# AFPGA_power.net
KiCad netlist of a schematic drawn in Altium Designer
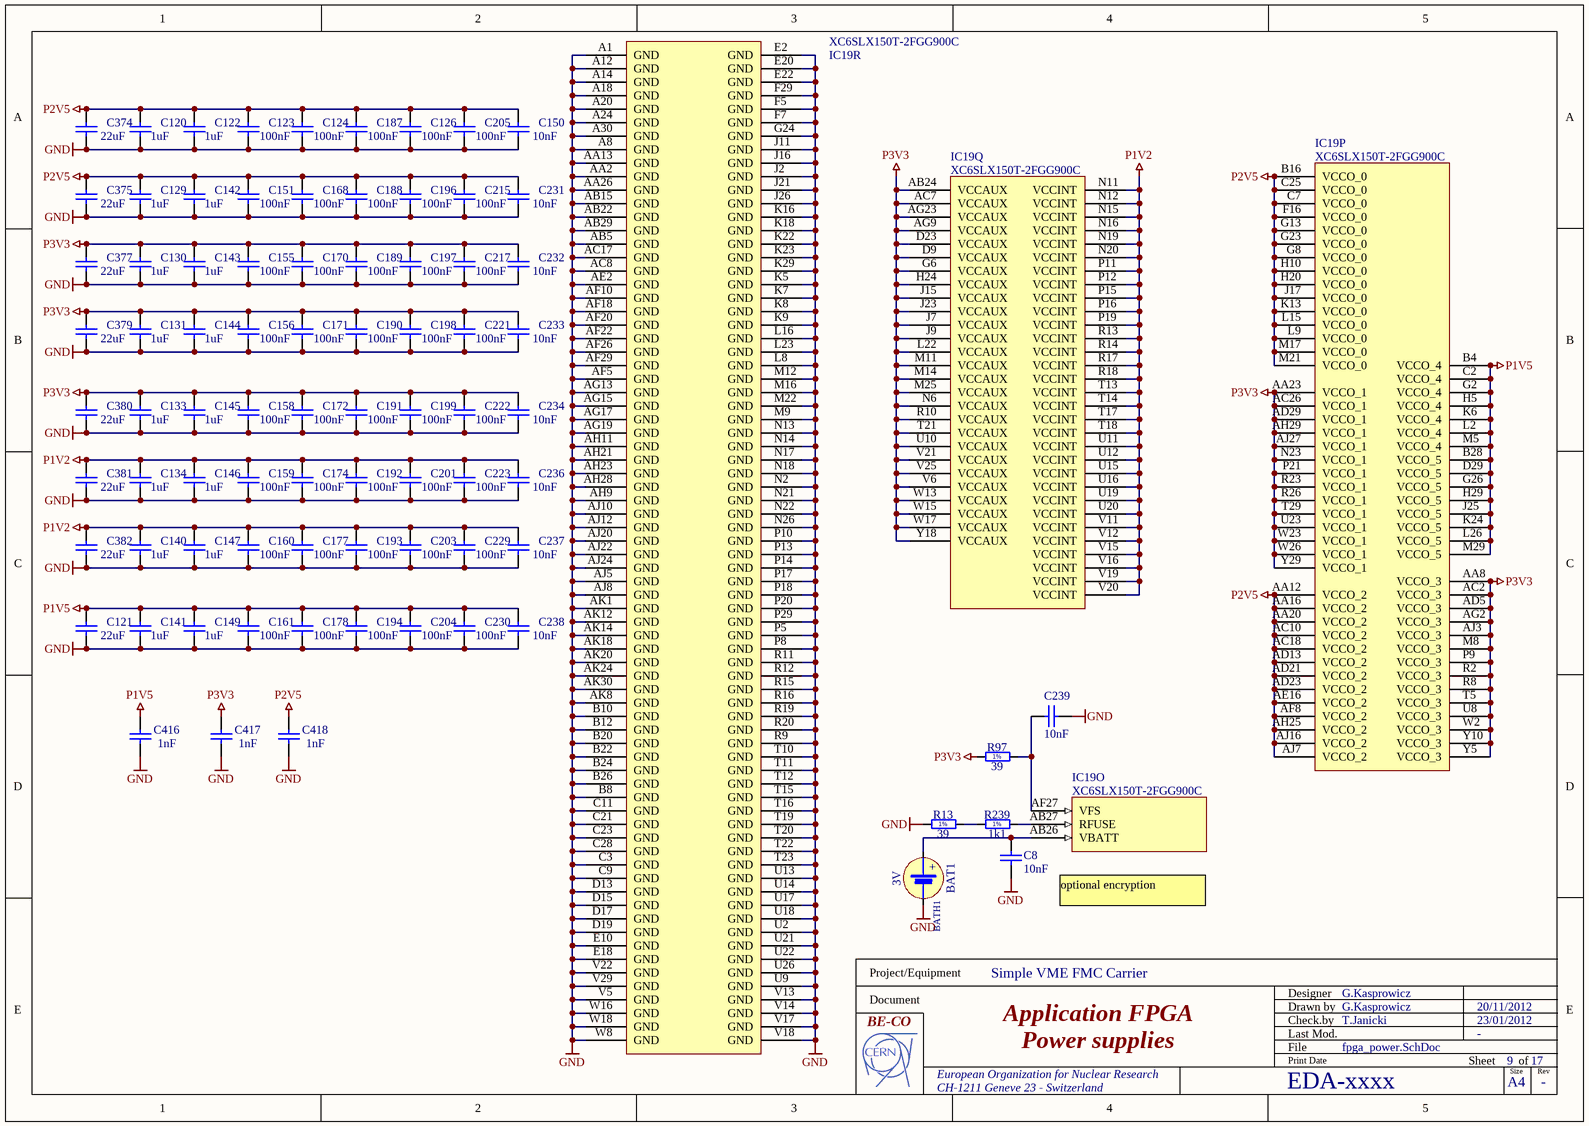
[diagram p0: AFPGA_power.SchDoc]

(export (version "E")
  (design (tool "Eeschema 10.0.6"))
  (components
    (comp (ref "BAT1")
      (value "3V")
      (footprint "BAT_VARTA_CR2025")
      (description "Battery for use only with Socket Holder")
      (fields
        (field (name "PART NUMBER") "BAT_VARTA_CR2025")
        (field (name "POWER") "165mAh")
        (field (name "AUTHOR") "CERN DEM JLC")
      )
      (libsource (lib "Eletro-mechanical") (part "Battery No Pin"))
    )
    (comp (ref "BATH1")
      (value "~")
      (footprint "BATH_KEYSTONE_103")
      (description "Battery Holder whit 2 Pin")
      (fields
        (field (name "PART NUMBER") "BATH_KEYSTONE_103")
        (field (name "MANUFACTURER") "KEYSTONE")
        (field (name "AUTHOR") "CERN DEM JLC")
      )
      (libsource (lib "Eletro-mechanical") (part "Battery Holder 2 Pin"))
    )
    (comp (ref "C8")
      (value "10nF")
      (footprint "CAPC1608X87N")
      (description "Non-polarised capacitor")
      (fields
        (field (name "PART NUMBER") "CC0603_10NF_50V_10%_X7R")
        (field (name "VOLTAGE") "50V")
        (field (name "AUTHOR") "CERN DEM JLC")
      )
      (libsource (lib "Capacitors") (part "Capacitor - non polarized"))
    )
    (comp (ref "C120")
      (value "1uF")
      (footprint "CAPC1608X87N")
      (description "Non-polarised capacitor")
      (fields
        (field (name "PART NUMBER") "CC0603_1UF_16V_10%_X7R")
        (field (name "VOLTAGE") "16V")
        (field (name "AUTHOR") "CERN DEM JLC")
      )
      (libsource (lib "Capacitors") (part "Capacitor - non polarized"))
    )
    (comp (ref "C121")
      (value "22uF")
      (footprint "CAPC3216X180N")
      (description "Non-polarised capacitor")
      (fields
        (field (name "PART NUMBER") "CC1206_22UF_10V_10%_X7R")
        (field (name "VOLTAGE") "10V")
        (field (name "AUTHOR") "CERN DEM JLC")
      )
      (libsource (lib "Capacitors") (part "Capacitor - non polarized"))
    )
    (comp (ref "C122")
      (value "1uF")
      (footprint "CAPC1608X87N")
      (description "Non-polarised capacitor")
      (fields
        (field (name "PART NUMBER") "CC0603_1UF_16V_10%_X7R")
        (field (name "VOLTAGE") "16V")
        (field (name "AUTHOR") "CERN DEM JLC")
      )
      (libsource (lib "Capacitors") (part "Capacitor - non polarized"))
    )
    (comp (ref "C123")
      (value "100nF")
      (footprint "CAPC1005X55N")
      (description "Non-polarised capacitor")
      (fields
        (field (name "PART NUMBER") "CC0402_100NF_16V_10%_X7R")
        (field (name "VOLTAGE") "16V")
        (field (name "AUTHOR") "CERN DEM JLC")
      )
      (libsource (lib "Capacitors") (part "Capacitor - non polarized"))
    )
    (comp (ref "C124")
      (value "100nF")
      (footprint "CAPC1005X55N")
      (description "Non-polarised capacitor")
      (fields
        (field (name "PART NUMBER") "CC0402_100NF_16V_10%_X7R")
        (field (name "VOLTAGE") "16V")
        (field (name "AUTHOR") "CERN DEM JLC")
      )
      (libsource (lib "Capacitors") (part "Capacitor - non polarized"))
    )
    (comp (ref "C126")
      (value "100nF")
      (footprint "CAPC1005X55N")
      (description "Non-polarised capacitor")
      (fields
        (field (name "PART NUMBER") "CC0402_100NF_16V_10%_X7R")
        (field (name "VOLTAGE") "16V")
        (field (name "AUTHOR") "CERN DEM JLC")
      )
      (libsource (lib "Capacitors") (part "Capacitor - non polarized"))
    )
    (comp (ref "C129")
      (value "1uF")
      (footprint "CAPC1608X87N")
      (description "Non-polarised capacitor")
      (fields
        (field (name "PART NUMBER") "CC0603_1UF_16V_10%_X7R")
        (field (name "VOLTAGE") "16V")
        (field (name "AUTHOR") "CERN DEM JLC")
      )
      (libsource (lib "Capacitors") (part "Capacitor - non polarized"))
    )
    (comp (ref "C130")
      (value "1uF")
      (footprint "CAPC1608X87N")
      (description "Non-polarised capacitor")
      (fields
        (field (name "PART NUMBER") "CC0603_1UF_16V_10%_X7R")
        (field (name "VOLTAGE") "16V")
        (field (name "AUTHOR") "CERN DEM JLC")
      )
      (libsource (lib "Capacitors") (part "Capacitor - non polarized"))
    )
    (comp (ref "C131")
      (value "1uF")
      (footprint "CAPC1608X87N")
      (description "Non-polarised capacitor")
      (fields
        (field (name "PART NUMBER") "CC0603_1UF_16V_10%_X7R")
        (field (name "VOLTAGE") "16V")
        (field (name "AUTHOR") "CERN DEM JLC")
      )
      (libsource (lib "Capacitors") (part "Capacitor - non polarized"))
    )
    (comp (ref "C133")
      (value "1uF")
      (footprint "CAPC1608X87N")
      (description "Non-polarised capacitor")
      (fields
        (field (name "PART NUMBER") "CC0603_1UF_16V_10%_X7R")
        (field (name "VOLTAGE") "16V")
        (field (name "AUTHOR") "CERN DEM JLC")
      )
      (libsource (lib "Capacitors") (part "Capacitor - non polarized"))
    )
    (comp (ref "C134")
      (value "1uF")
      (footprint "CAPC1608X87N")
      (description "Non-polarised capacitor")
      (fields
        (field (name "PART NUMBER") "CC0603_1UF_16V_10%_X7R")
        (field (name "VOLTAGE") "16V")
        (field (name "AUTHOR") "CERN DEM JLC")
      )
      (libsource (lib "Capacitors") (part "Capacitor - non polarized"))
    )
    (comp (ref "C140")
      (value "1uF")
      (footprint "CAPC1608X87N")
      (description "Non-polarised capacitor")
      (fields
        (field (name "PART NUMBER") "CC0603_1UF_16V_10%_X7R")
        (field (name "VOLTAGE") "16V")
        (field (name "AUTHOR") "CERN DEM JLC")
      )
      (libsource (lib "Capacitors") (part "Capacitor - non polarized"))
    )
    (comp (ref "C141")
      (value "1uF")
      (footprint "CAPC1608X87N")
      (description "Non-polarised capacitor")
      (fields
        (field (name "PART NUMBER") "CC0603_1UF_16V_10%_X7R")
        (field (name "VOLTAGE") "16V")
        (field (name "AUTHOR") "CERN DEM JLC")
      )
      (libsource (lib "Capacitors") (part "Capacitor - non polarized"))
    )
    (comp (ref "C142")
      (value "1uF")
      (footprint "CAPC1608X87N")
      (description "Non-polarised capacitor")
      (fields
        (field (name "PART NUMBER") "CC0603_1UF_16V_10%_X7R")
        (field (name "VOLTAGE") "16V")
        (field (name "AUTHOR") "CERN DEM JLC")
      )
      (libsource (lib "Capacitors") (part "Capacitor - non polarized"))
    )
    (comp (ref "C143")
      (value "1uF")
      (footprint "CAPC1608X87N")
      (description "Non-polarised capacitor")
      (fields
        (field (name "PART NUMBER") "CC0603_1UF_16V_10%_X7R")
        (field (name "VOLTAGE") "16V")
        (field (name "AUTHOR") "CERN DEM JLC")
      )
      (libsource (lib "Capacitors") (part "Capacitor - non polarized"))
    )
    (comp (ref "C144")
      (value "1uF")
      (footprint "CAPC1608X87N")
      (description "Non-polarised capacitor")
      (fields
        (field (name "PART NUMBER") "CC0603_1UF_16V_10%_X7R")
        (field (name "VOLTAGE") "16V")
        (field (name "AUTHOR") "CERN DEM JLC")
      )
      (libsource (lib "Capacitors") (part "Capacitor - non polarized"))
    )
    (comp (ref "C145")
      (value "1uF")
      (footprint "CAPC1608X87N")
      (description "Non-polarised capacitor")
      (fields
        (field (name "PART NUMBER") "CC0603_1UF_16V_10%_X7R")
        (field (name "VOLTAGE") "16V")
        (field (name "AUTHOR") "CERN DEM JLC")
      )
      (libsource (lib "Capacitors") (part "Capacitor - non polarized"))
    )
    (comp (ref "C146")
      (value "1uF")
      (footprint "CAPC1608X87N")
      (description "Non-polarised capacitor")
      (fields
        (field (name "PART NUMBER") "CC0603_1UF_16V_10%_X7R")
        (field (name "VOLTAGE") "16V")
        (field (name "AUTHOR") "CERN DEM JLC")
      )
      (libsource (lib "Capacitors") (part "Capacitor - non polarized"))
    )
    (comp (ref "C147")
      (value "1uF")
      (footprint "CAPC1608X87N")
      (description "Non-polarised capacitor")
      (fields
        (field (name "PART NUMBER") "CC0603_1UF_16V_10%_X7R")
        (field (name "VOLTAGE") "16V")
        (field (name "AUTHOR") "CERN DEM JLC")
      )
      (libsource (lib "Capacitors") (part "Capacitor - non polarized"))
    )
    (comp (ref "C149")
      (value "1uF")
      (footprint "CAPC1608X87N")
      (description "Non-polarised capacitor")
      (fields
        (field (name "PART NUMBER") "CC0603_1UF_16V_10%_X7R")
        (field (name "VOLTAGE") "16V")
        (field (name "AUTHOR") "CERN DEM JLC")
      )
      (libsource (lib "Capacitors") (part "Capacitor - non polarized"))
    )
    (comp (ref "C150")
      (value "10nF")
      (footprint "CAPC1608X87N")
      (description "Non-polarised capacitor")
      (fields
        (field (name "PART NUMBER") "CC0603_10NF_50V_10%_X7R")
        (field (name "VOLTAGE") "50V")
        (field (name "AUTHOR") "CERN DEM JLC")
      )
      (libsource (lib "Capacitors") (part "Capacitor - non polarized"))
    )
    (comp (ref "C151")
      (value "100nF")
      (footprint "CAPC1005X55N")
      (description "Non-polarised capacitor")
      (fields
        (field (name "PART NUMBER") "CC0402_100NF_16V_10%_X7R")
        (field (name "VOLTAGE") "16V")
        (field (name "AUTHOR") "CERN DEM JLC")
      )
      (libsource (lib "Capacitors") (part "Capacitor - non polarized"))
    )
    (comp (ref "C155")
      (value "100nF")
      (footprint "CAPC1005X55N")
      (description "Non-polarised capacitor")
      (fields
        (field (name "PART NUMBER") "CC0402_100NF_16V_10%_X7R")
        (field (name "VOLTAGE") "16V")
        (field (name "AUTHOR") "CERN DEM JLC")
      )
      (libsource (lib "Capacitors") (part "Capacitor - non polarized"))
    )
    (comp (ref "C156")
      (value "100nF")
      (footprint "CAPC1005X55N")
      (description "Non-polarised capacitor")
      (fields
        (field (name "PART NUMBER") "CC0402_100NF_16V_10%_X7R")
        (field (name "VOLTAGE") "16V")
        (field (name "AUTHOR") "CERN DEM JLC")
      )
      (libsource (lib "Capacitors") (part "Capacitor - non polarized"))
    )
    (comp (ref "C158")
      (value "100nF")
      (footprint "CAPC1005X55N")
      (description "Non-polarised capacitor")
      (fields
        (field (name "PART NUMBER") "CC0402_100NF_16V_10%_X7R")
        (field (name "VOLTAGE") "16V")
        (field (name "AUTHOR") "CERN DEM JLC")
      )
      (libsource (lib "Capacitors") (part "Capacitor - non polarized"))
    )
    (comp (ref "C159")
      (value "100nF")
      (footprint "CAPC1005X55N")
      (description "Non-polarised capacitor")
      (fields
        (field (name "PART NUMBER") "CC0402_100NF_16V_10%_X7R")
        (field (name "VOLTAGE") "16V")
        (field (name "AUTHOR") "CERN DEM JLC")
      )
      (libsource (lib "Capacitors") (part "Capacitor - non polarized"))
    )
    (comp (ref "C160")
      (value "100nF")
      (footprint "CAPC1005X55N")
      (description "Non-polarised capacitor")
      (fields
        (field (name "PART NUMBER") "CC0402_100NF_16V_10%_X7R")
        (field (name "VOLTAGE") "16V")
        (field (name "AUTHOR") "CERN DEM JLC")
      )
      (libsource (lib "Capacitors") (part "Capacitor - non polarized"))
    )
    (comp (ref "C161")
      (value "100nF")
      (footprint "CAPC1005X55N")
      (description "Non-polarised capacitor")
      (fields
        (field (name "PART NUMBER") "CC0402_100NF_16V_10%_X7R")
        (field (name "VOLTAGE") "16V")
        (field (name "AUTHOR") "CERN DEM JLC")
      )
      (libsource (lib "Capacitors") (part "Capacitor - non polarized"))
    )
    (comp (ref "C168")
      (value "100nF")
      (footprint "CAPC1005X55N")
      (description "Non-polarised capacitor")
      (fields
        (field (name "PART NUMBER") "CC0402_100NF_16V_10%_X7R")
        (field (name "VOLTAGE") "16V")
        (field (name "AUTHOR") "CERN DEM JLC")
      )
      (libsource (lib "Capacitors") (part "Capacitor - non polarized"))
    )
    (comp (ref "C170")
      (value "100nF")
      (footprint "CAPC1005X55N")
      (description "Non-polarised capacitor")
      (fields
        (field (name "PART NUMBER") "CC0402_100NF_16V_10%_X7R")
        (field (name "VOLTAGE") "16V")
        (field (name "AUTHOR") "CERN DEM JLC")
      )
      (libsource (lib "Capacitors") (part "Capacitor - non polarized"))
    )
    (comp (ref "C171")
      (value "100nF")
      (footprint "CAPC1005X55N")
      (description "Non-polarised capacitor")
      (fields
        (field (name "PART NUMBER") "CC0402_100NF_16V_10%_X7R")
        (field (name "VOLTAGE") "16V")
        (field (name "AUTHOR") "CERN DEM JLC")
      )
      (libsource (lib "Capacitors") (part "Capacitor - non polarized"))
    )
    (comp (ref "C172")
      (value "100nF")
      (footprint "CAPC1005X55N")
      (description "Non-polarised capacitor")
      (fields
        (field (name "PART NUMBER") "CC0402_100NF_16V_10%_X7R")
        (field (name "VOLTAGE") "16V")
        (field (name "AUTHOR") "CERN DEM JLC")
      )
      (libsource (lib "Capacitors") (part "Capacitor - non polarized"))
    )
    (comp (ref "C174")
      (value "100nF")
      (footprint "CAPC1005X55N")
      (description "Non-polarised capacitor")
      (fields
        (field (name "PART NUMBER") "CC0402_100NF_16V_10%_X7R")
        (field (name "VOLTAGE") "16V")
        (field (name "AUTHOR") "CERN DEM JLC")
      )
      (libsource (lib "Capacitors") (part "Capacitor - non polarized"))
    )
    (comp (ref "C177")
      (value "100nF")
      (footprint "CAPC1005X55N")
      (description "Non-polarised capacitor")
      (fields
        (field (name "PART NUMBER") "CC0402_100NF_16V_10%_X7R")
        (field (name "VOLTAGE") "16V")
        (field (name "AUTHOR") "CERN DEM JLC")
      )
      (libsource (lib "Capacitors") (part "Capacitor - non polarized"))
    )
    (comp (ref "C178")
      (value "100nF")
      (footprint "CAPC1005X55N")
      (description "Non-polarised capacitor")
      (fields
        (field (name "PART NUMBER") "CC0402_100NF_16V_10%_X7R")
        (field (name "VOLTAGE") "16V")
        (field (name "AUTHOR") "CERN DEM JLC")
      )
      (libsource (lib "Capacitors") (part "Capacitor - non polarized"))
    )
    (comp (ref "C187")
      (value "100nF")
      (footprint "CAPC1005X55N")
      (description "Non-polarised capacitor")
      (fields
        (field (name "PART NUMBER") "CC0402_100NF_16V_10%_X7R")
        (field (name "VOLTAGE") "16V")
        (field (name "AUTHOR") "CERN DEM JLC")
      )
      (libsource (lib "Capacitors") (part "Capacitor - non polarized"))
    )
    (comp (ref "C188")
      (value "100nF")
      (footprint "CAPC1005X55N")
      (description "Non-polarised capacitor")
      (fields
        (field (name "PART NUMBER") "CC0402_100NF_16V_10%_X7R")
        (field (name "VOLTAGE") "16V")
        (field (name "AUTHOR") "CERN DEM JLC")
      )
      (libsource (lib "Capacitors") (part "Capacitor - non polarized"))
    )
    (comp (ref "C189")
      (value "100nF")
      (footprint "CAPC1005X55N")
      (description "Non-polarised capacitor")
      (fields
        (field (name "PART NUMBER") "CC0402_100NF_16V_10%_X7R")
        (field (name "VOLTAGE") "16V")
        (field (name "AUTHOR") "CERN DEM JLC")
      )
      (libsource (lib "Capacitors") (part "Capacitor - non polarized"))
    )
    (comp (ref "C190")
      (value "100nF")
      (footprint "CAPC1005X55N")
      (description "Non-polarised capacitor")
      (fields
        (field (name "PART NUMBER") "CC0402_100NF_16V_10%_X7R")
        (field (name "VOLTAGE") "16V")
        (field (name "AUTHOR") "CERN DEM JLC")
      )
      (libsource (lib "Capacitors") (part "Capacitor - non polarized"))
    )
    (comp (ref "C191")
      (value "100nF")
      (footprint "CAPC1005X55N")
      (description "Non-polarised capacitor")
      (fields
        (field (name "PART NUMBER") "CC0402_100NF_16V_10%_X7R")
        (field (name "VOLTAGE") "16V")
        (field (name "AUTHOR") "CERN DEM JLC")
      )
      (libsource (lib "Capacitors") (part "Capacitor - non polarized"))
    )
    (comp (ref "C192")
      (value "100nF")
      (footprint "CAPC1005X55N")
      (description "Non-polarised capacitor")
      (fields
        (field (name "PART NUMBER") "CC0402_100NF_16V_10%_X7R")
        (field (name "VOLTAGE") "16V")
        (field (name "AUTHOR") "CERN DEM JLC")
      )
      (libsource (lib "Capacitors") (part "Capacitor - non polarized"))
    )
    (comp (ref "C193")
      (value "100nF")
      (footprint "CAPC1005X55N")
      (description "Non-polarised capacitor")
      (fields
        (field (name "PART NUMBER") "CC0402_100NF_16V_10%_X7R")
        (field (name "VOLTAGE") "16V")
        (field (name "AUTHOR") "CERN DEM JLC")
      )
      (libsource (lib "Capacitors") (part "Capacitor - non polarized"))
    )
    (comp (ref "C194")
      (value "100nF")
      (footprint "CAPC1005X55N")
      (description "Non-polarised capacitor")
      (fields
        (field (name "PART NUMBER") "CC0402_100NF_16V_10%_X7R")
        (field (name "VOLTAGE") "16V")
        (field (name "AUTHOR") "CERN DEM JLC")
      )
      (libsource (lib "Capacitors") (part "Capacitor - non polarized"))
    )
    (comp (ref "C196")
      (value "100nF")
      (footprint "CAPC1005X55N")
      (description "Non-polarised capacitor")
      (fields
        (field (name "PART NUMBER") "CC0402_100NF_16V_10%_X7R")
        (field (name "VOLTAGE") "16V")
        (field (name "AUTHOR") "CERN DEM JLC")
      )
      (libsource (lib "Capacitors") (part "Capacitor - non polarized"))
    )
    (comp (ref "C197")
      (value "100nF")
      (footprint "CAPC1005X55N")
      (description "Non-polarised capacitor")
      (fields
        (field (name "PART NUMBER") "CC0402_100NF_16V_10%_X7R")
        (field (name "VOLTAGE") "16V")
        (field (name "AUTHOR") "CERN DEM JLC")
      )
      (libsource (lib "Capacitors") (part "Capacitor - non polarized"))
    )
    (comp (ref "C198")
      (value "100nF")
      (footprint "CAPC1005X55N")
      (description "Non-polarised capacitor")
      (fields
        (field (name "PART NUMBER") "CC0402_100NF_16V_10%_X7R")
        (field (name "VOLTAGE") "16V")
        (field (name "AUTHOR") "CERN DEM JLC")
      )
      (libsource (lib "Capacitors") (part "Capacitor - non polarized"))
    )
    (comp (ref "C199")
      (value "100nF")
      (footprint "CAPC1005X55N")
      (description "Non-polarised capacitor")
      (fields
        (field (name "PART NUMBER") "CC0402_100NF_16V_10%_X7R")
        (field (name "VOLTAGE") "16V")
        (field (name "AUTHOR") "CERN DEM JLC")
      )
      (libsource (lib "Capacitors") (part "Capacitor - non polarized"))
    )
    (comp (ref "C201")
      (value "100nF")
      (footprint "CAPC1005X55N")
      (description "Non-polarised capacitor")
      (fields
        (field (name "PART NUMBER") "CC0402_100NF_16V_10%_X7R")
        (field (name "VOLTAGE") "16V")
        (field (name "AUTHOR") "CERN DEM JLC")
      )
      (libsource (lib "Capacitors") (part "Capacitor - non polarized"))
    )
    (comp (ref "C203")
      (value "100nF")
      (footprint "CAPC1005X55N")
      (description "Non-polarised capacitor")
      (fields
        (field (name "PART NUMBER") "CC0402_100NF_16V_10%_X7R")
        (field (name "VOLTAGE") "16V")
        (field (name "AUTHOR") "CERN DEM JLC")
      )
      (libsource (lib "Capacitors") (part "Capacitor - non polarized"))
    )
    (comp (ref "C204")
      (value "100nF")
      (footprint "CAPC1005X55N")
      (description "Non-polarised capacitor")
      (fields
        (field (name "PART NUMBER") "CC0402_100NF_16V_10%_X7R")
        (field (name "VOLTAGE") "16V")
        (field (name "AUTHOR") "CERN DEM JLC")
      )
      (libsource (lib "Capacitors") (part "Capacitor - non polarized"))
    )
    (comp (ref "C205")
      (value "100nF")
      (footprint "CAPC1005X55N")
      (description "Non-polarised capacitor")
      (fields
        (field (name "PART NUMBER") "CC0402_100NF_16V_10%_X7R")
        (field (name "VOLTAGE") "16V")
        (field (name "AUTHOR") "CERN DEM JLC")
      )
      (libsource (lib "Capacitors") (part "Capacitor - non polarized"))
    )
    (comp (ref "C215")
      (value "100nF")
      (footprint "CAPC1005X55N")
      (description "Non-polarised capacitor")
      (fields
        (field (name "PART NUMBER") "CC0402_100NF_16V_10%_X7R")
        (field (name "VOLTAGE") "16V")
        (field (name "AUTHOR") "CERN DEM JLC")
      )
      (libsource (lib "Capacitors") (part "Capacitor - non polarized"))
    )
    (comp (ref "C217")
      (value "100nF")
      (footprint "CAPC1005X55N")
      (description "Non-polarised capacitor")
      (fields
        (field (name "PART NUMBER") "CC0402_100NF_16V_10%_X7R")
        (field (name "VOLTAGE") "16V")
        (field (name "AUTHOR") "CERN DEM JLC")
      )
      (libsource (lib "Capacitors") (part "Capacitor - non polarized"))
    )
    (comp (ref "C221")
      (value "100nF")
      (footprint "CAPC1005X55N")
      (description "Non-polarised capacitor")
      (fields
        (field (name "PART NUMBER") "CC0402_100NF_16V_10%_X7R")
        (field (name "VOLTAGE") "16V")
        (field (name "AUTHOR") "CERN DEM JLC")
      )
      (libsource (lib "Capacitors") (part "Capacitor - non polarized"))
    )
    (comp (ref "C222")
      (value "100nF")
      (footprint "CAPC1005X55N")
      (description "Non-polarised capacitor")
      (fields
        (field (name "PART NUMBER") "CC0402_100NF_16V_10%_X7R")
        (field (name "VOLTAGE") "16V")
        (field (name "AUTHOR") "CERN DEM JLC")
      )
      (libsource (lib "Capacitors") (part "Capacitor - non polarized"))
    )
    (comp (ref "C223")
      (value "100nF")
      (footprint "CAPC1005X55N")
      (description "Non-polarised capacitor")
      (fields
        (field (name "PART NUMBER") "CC0402_100NF_16V_10%_X7R")
        (field (name "VOLTAGE") "16V")
        (field (name "AUTHOR") "CERN DEM JLC")
      )
      (libsource (lib "Capacitors") (part "Capacitor - non polarized"))
    )
    (comp (ref "C229")
      (value "100nF")
      (footprint "CAPC1005X55N")
      (description "Non-polarised capacitor")
      (fields
        (field (name "PART NUMBER") "CC0402_100NF_16V_10%_X7R")
        (field (name "VOLTAGE") "16V")
        (field (name "AUTHOR") "CERN DEM JLC")
      )
      (libsource (lib "Capacitors") (part "Capacitor - non polarized"))
    )
    (comp (ref "C230")
      (value "100nF")
      (footprint "CAPC1005X55N")
      (description "Non-polarised capacitor")
      (fields
        (field (name "PART NUMBER") "CC0402_100NF_16V_10%_X7R")
        (field (name "VOLTAGE") "16V")
        (field (name "AUTHOR") "CERN DEM JLC")
      )
      (libsource (lib "Capacitors") (part "Capacitor - non polarized"))
    )
    (comp (ref "C231")
      (value "10nF")
      (footprint "CAPC1608X87N")
      (description "Non-polarised capacitor")
      (fields
        (field (name "PART NUMBER") "CC0603_10NF_50V_10%_X7R")
        (field (name "VOLTAGE") "50V")
        (field (name "AUTHOR") "CERN DEM JLC")
      )
      (libsource (lib "Capacitors") (part "Capacitor - non polarized"))
    )
    (comp (ref "C232")
      (value "10nF")
      (footprint "CAPC1608X87N")
      (description "Non-polarised capacitor")
      (fields
        (field (name "PART NUMBER") "CC0603_10NF_50V_10%_X7R")
        (field (name "VOLTAGE") "50V")
        (field (name "AUTHOR") "CERN DEM JLC")
      )
      (libsource (lib "Capacitors") (part "Capacitor - non polarized"))
    )
    (comp (ref "C233")
      (value "10nF")
      (footprint "CAPC1608X87N")
      (description "Non-polarised capacitor")
      (fields
        (field (name "PART NUMBER") "CC0603_10NF_50V_10%_X7R")
        (field (name "VOLTAGE") "50V")
        (field (name "AUTHOR") "CERN DEM JLC")
      )
      (libsource (lib "Capacitors") (part "Capacitor - non polarized"))
    )
    (comp (ref "C234")
      (value "10nF")
      (footprint "CAPC1608X87N")
      (description "Non-polarised capacitor")
      (fields
        (field (name "PART NUMBER") "CC0603_10NF_50V_10%_X7R")
        (field (name "VOLTAGE") "50V")
        (field (name "AUTHOR") "CERN DEM JLC")
      )
      (libsource (lib "Capacitors") (part "Capacitor - non polarized"))
    )
    (comp (ref "C236")
      (value "10nF")
      (footprint "CAPC1608X87N")
      (description "Non-polarised capacitor")
      (fields
        (field (name "PART NUMBER") "CC0603_10NF_50V_10%_X7R")
        (field (name "VOLTAGE") "50V")
        (field (name "AUTHOR") "CERN DEM JLC")
      )
      (libsource (lib "Capacitors") (part "Capacitor - non polarized"))
    )
    (comp (ref "C237")
      (value "10nF")
      (footprint "CAPC1608X87N")
      (description "Non-polarised capacitor")
      (fields
        (field (name "PART NUMBER") "CC0603_10NF_50V_10%_X7R")
        (field (name "VOLTAGE") "50V")
        (field (name "AUTHOR") "CERN DEM JLC")
      )
      (libsource (lib "Capacitors") (part "Capacitor - non polarized"))
    )
    (comp (ref "C238")
      (value "10nF")
      (footprint "CAPC1608X87N")
      (description "Non-polarised capacitor")
      (fields
        (field (name "PART NUMBER") "CC0603_10NF_50V_10%_X7R")
        (field (name "VOLTAGE") "50V")
        (field (name "AUTHOR") "CERN DEM JLC")
      )
      (libsource (lib "Capacitors") (part "Capacitor - non polarized"))
    )
    (comp (ref "C239")
      (value "10nF")
      (footprint "CAPC1608X87N")
      (description "Non-polarised capacitor")
      (fields
        (field (name "PART NUMBER") "CC0603_10NF_50V_10%_X7R")
        (field (name "VOLTAGE") "50V")
        (field (name "AUTHOR") "CERN DEM JLC")
      )
      (libsource (lib "Capacitors") (part "Capacitor - non polarized"))
    )
    (comp (ref "C374")
      (value "22uF")
      (footprint "CAPC3216X180N")
      (description "Non-polarised capacitor")
      (fields
        (field (name "PART NUMBER") "CC1206_22UF_10V_10%_X7R")
        (field (name "VOLTAGE") "10V")
        (field (name "AUTHOR") "CERN DEM JLC")
      )
      (libsource (lib "Capacitors") (part "Capacitor - non polarized"))
    )
    (comp (ref "C375")
      (value "22uF")
      (footprint "CAPC3216X180N")
      (description "Non-polarised capacitor")
      (fields
        (field (name "PART NUMBER") "CC1206_22UF_10V_10%_X7R")
        (field (name "VOLTAGE") "10V")
        (field (name "AUTHOR") "CERN DEM JLC")
      )
      (libsource (lib "Capacitors") (part "Capacitor - non polarized"))
    )
    (comp (ref "C377")
      (value "22uF")
      (footprint "CAPC3216X180N")
      (description "Non-polarised capacitor")
      (fields
        (field (name "PART NUMBER") "CC1206_22UF_10V_10%_X7R")
        (field (name "VOLTAGE") "10V")
        (field (name "AUTHOR") "CERN DEM JLC")
      )
      (libsource (lib "Capacitors") (part "Capacitor - non polarized"))
    )
    (comp (ref "C379")
      (value "22uF")
      (footprint "CAPC3216X180N")
      (description "Non-polarised capacitor")
      (fields
        (field (name "PART NUMBER") "CC1206_22UF_10V_10%_X7R")
        (field (name "VOLTAGE") "10V")
        (field (name "AUTHOR") "CERN DEM JLC")
      )
      (libsource (lib "Capacitors") (part "Capacitor - non polarized"))
    )
    (comp (ref "C380")
      (value "22uF")
      (footprint "CAPC3216X180N")
      (description "Non-polarised capacitor")
      (fields
        (field (name "PART NUMBER") "CC1206_22UF_10V_10%_X7R")
        (field (name "VOLTAGE") "10V")
        (field (name "AUTHOR") "CERN DEM JLC")
      )
      (libsource (lib "Capacitors") (part "Capacitor - non polarized"))
    )
    (comp (ref "C381")
      (value "22uF")
      (footprint "CAPC3216X180N")
      (description "Non-polarised capacitor")
      (fields
        (field (name "PART NUMBER") "CC1206_22UF_10V_10%_X7R")
        (field (name "VOLTAGE") "10V")
        (field (name "AUTHOR") "CERN DEM JLC")
      )
      (libsource (lib "Capacitors") (part "Capacitor - non polarized"))
    )
    (comp (ref "C382")
      (value "22uF")
      (footprint "CAPC3216X180N")
      (description "Non-polarised capacitor")
      (fields
        (field (name "PART NUMBER") "CC1206_22UF_10V_10%_X7R")
        (field (name "VOLTAGE") "10V")
        (field (name "AUTHOR") "CERN DEM JLC")
      )
      (libsource (lib "Capacitors") (part "Capacitor - non polarized"))
    )
    (comp (ref "C416")
      (value "1nF")
      (footprint "CAPC1005X55N")
      (description "Non-polarised capacitor")
      (fields
        (field (name "PART NUMBER") "CC0402_1NF_50V_10%_X7R")
        (field (name "VOLTAGE") "50V")
        (field (name "AUTHOR") "CERN DEM JLC")
      )
      (libsource (lib "Capacitors") (part "Capacitor - non polarized"))
    )
    (comp (ref "C417")
      (value "1nF")
      (footprint "CAPC1005X55N")
      (description "Non-polarised capacitor")
      (fields
        (field (name "PART NUMBER") "CC0402_1NF_50V_10%_X7R")
        (field (name "VOLTAGE") "50V")
        (field (name "AUTHOR") "CERN DEM JLC")
      )
      (libsource (lib "Capacitors") (part "Capacitor - non polarized"))
    )
    (comp (ref "C418")
      (value "1nF")
      (footprint "CAPC1005X55N")
      (description "Non-polarised capacitor")
      (fields
        (field (name "PART NUMBER") "CC0402_1NF_50V_10%_X7R")
        (field (name "VOLTAGE") "50V")
        (field (name "AUTHOR") "CERN DEM JLC")
      )
      (libsource (lib "Capacitors") (part "Capacitor - non polarized"))
    )
    (comp (ref "IC19")
      (value "XC6SLX150T-2FGG900C")
      (footprint "BGA900C100P30X30_3100X3100X260")
      (description "SPARTAN-6, FPGA, 900-Ball BGA, Commercial Grade, Pb-Free")
      (fields (field (name "MANUFACTURER") "XILINX") (field (name "AUTHOR") "CERN DEM JLC"))
      (libsource (lib "ICs And Semiconductors") (part "XC6SLX150T-2FGG900C"))
    )
    (comp (ref "R13")
      (value "39")
      (footprint "RESC1608X55N")
      (description "Resistor - 1%")
      (fields
        (field (name "PART NUMBER") "R0603_39R_1%_0.1W_100PPM")
        (field (name "POWER") "0.1W")
        (field (name "AUTHOR") "CERN DEM JLC")
      )
      (libsource (lib "Resistors") (part "Resistor - 1%"))
    )
    (comp (ref "R97")
      (value "39")
      (footprint "RESC1608X55N")
      (description "Resistor - 1%")
      (fields
        (field (name "PART NUMBER") "R0603_39R_1%_0.1W_100PPM")
        (field (name "POWER") "0.1W")
        (field (name "AUTHOR") "CERN DEM JLC")
      )
      (libsource (lib "Resistors") (part "Resistor - 1%"))
    )
    (comp (ref "R239")
      (value "1k1")
      (footprint "RESC1608X55N")
      (description "Resistor - 1%")
      (fields
        (field (name "PART NUMBER") "R0603_1K1_1%_0.1W_100PPM")
        (field (name "POWER") "0.1W")
        (field (name "AUTHOR") "CERN DEM JLC")
      )
      (libsource (lib "Resistors") (part "Resistor - 1%"))
    )
  )
  (nets
    (net (code "1") (name "GND") (class "Default")
      (node (ref "BATH1") (pin "2") (pinfunction "MINUS_2") (pintype "passive"))
      (node (ref "C120") (pin "1") (pinfunction "1_1") (pintype "passive"))
      (node (ref "C121") (pin "1") (pinfunction "1_1") (pintype "passive"))
      (node (ref "C122") (pin "1") (pinfunction "1_1") (pintype "passive"))
      (node (ref "C123") (pin "1") (pinfunction "1_1") (pintype "passive"))
      (node (ref "C124") (pin "1") (pinfunction "1_1") (pintype "passive"))
      (node (ref "C126") (pin "1") (pinfunction "1_1") (pintype "passive"))
      (node (ref "C129") (pin "1") (pinfunction "1_1") (pintype "passive"))
      (node (ref "C130") (pin "1") (pinfunction "1_1") (pintype "passive"))
      (node (ref "C131") (pin "1") (pinfunction "1_1") (pintype "passive"))
      (node (ref "C133") (pin "1") (pinfunction "1_1") (pintype "passive"))
      (node (ref "C134") (pin "1") (pinfunction "1_1") (pintype "passive"))
      (node (ref "C140") (pin "1") (pinfunction "1_1") (pintype "passive"))
      (node (ref "C141") (pin "1") (pinfunction "1_1") (pintype "passive"))
      (node (ref "C142") (pin "1") (pinfunction "1_1") (pintype "passive"))
      (node (ref "C143") (pin "1") (pinfunction "1_1") (pintype "passive"))
      (node (ref "C144") (pin "1") (pinfunction "1_1") (pintype "passive"))
      (node (ref "C145") (pin "1") (pinfunction "1_1") (pintype "passive"))
      (node (ref "C146") (pin "1") (pinfunction "1_1") (pintype "passive"))
      (node (ref "C147") (pin "1") (pinfunction "1_1") (pintype "passive"))
      (node (ref "C149") (pin "1") (pinfunction "1_1") (pintype "passive"))
      (node (ref "C150") (pin "1") (pinfunction "1_1") (pintype "passive"))
      (node (ref "C151") (pin "1") (pinfunction "1_1") (pintype "passive"))
      (node (ref "C155") (pin "1") (pinfunction "1_1") (pintype "passive"))
      (node (ref "C156") (pin "1") (pinfunction "1_1") (pintype "passive"))
      (node (ref "C158") (pin "1") (pinfunction "1_1") (pintype "passive"))
      (node (ref "C159") (pin "1") (pinfunction "1_1") (pintype "passive"))
      (node (ref "C160") (pin "1") (pinfunction "1_1") (pintype "passive"))
      (node (ref "C161") (pin "1") (pinfunction "1_1") (pintype "passive"))
      (node (ref "C168") (pin "1") (pinfunction "1_1") (pintype "passive"))
      (node (ref "C170") (pin "1") (pinfunction "1_1") (pintype "passive"))
      (node (ref "C171") (pin "1") (pinfunction "1_1") (pintype "passive"))
      (node (ref "C172") (pin "1") (pinfunction "1_1") (pintype "passive"))
      (node (ref "C174") (pin "1") (pinfunction "1_1") (pintype "passive"))
      (node (ref "C177") (pin "1") (pinfunction "1_1") (pintype "passive"))
      (node (ref "C178") (pin "1") (pinfunction "1_1") (pintype "passive"))
      (node (ref "C187") (pin "1") (pinfunction "1_1") (pintype "passive"))
      (node (ref "C188") (pin "1") (pinfunction "1_1") (pintype "passive"))
      (node (ref "C189") (pin "1") (pinfunction "1_1") (pintype "passive"))
      (node (ref "C190") (pin "1") (pinfunction "1_1") (pintype "passive"))
      (node (ref "C191") (pin "1") (pinfunction "1_1") (pintype "passive"))
      (node (ref "C192") (pin "1") (pinfunction "1_1") (pintype "passive"))
      (node (ref "C193") (pin "1") (pinfunction "1_1") (pintype "passive"))
      (node (ref "C194") (pin "1") (pinfunction "1_1") (pintype "passive"))
      (node (ref "C196") (pin "1") (pinfunction "1_1") (pintype "passive"))
      (node (ref "C197") (pin "1") (pinfunction "1_1") (pintype "passive"))
      (node (ref "C198") (pin "1") (pinfunction "1_1") (pintype "passive"))
      (node (ref "C199") (pin "1") (pinfunction "1_1") (pintype "passive"))
      (node (ref "C201") (pin "1") (pinfunction "1_1") (pintype "passive"))
      (node (ref "C203") (pin "1") (pinfunction "1_1") (pintype "passive"))
      (node (ref "C204") (pin "1") (pinfunction "1_1") (pintype "passive"))
      (node (ref "C205") (pin "1") (pinfunction "1_1") (pintype "passive"))
      (node (ref "C215") (pin "1") (pinfunction "1_1") (pintype "passive"))
      (node (ref "C217") (pin "1") (pinfunction "1_1") (pintype "passive"))
      (node (ref "C221") (pin "1") (pinfunction "1_1") (pintype "passive"))
      (node (ref "C222") (pin "1") (pinfunction "1_1") (pintype "passive"))
      (node (ref "C223") (pin "1") (pinfunction "1_1") (pintype "passive"))
      (node (ref "C229") (pin "1") (pinfunction "1_1") (pintype "passive"))
      (node (ref "C230") (pin "1") (pinfunction "1_1") (pintype "passive"))
      (node (ref "C231") (pin "1") (pinfunction "1_1") (pintype "passive"))
      (node (ref "C232") (pin "1") (pinfunction "1_1") (pintype "passive"))
      (node (ref "C233") (pin "1") (pinfunction "1_1") (pintype "passive"))
      (node (ref "C234") (pin "1") (pinfunction "1_1") (pintype "passive"))
      (node (ref "C236") (pin "1") (pinfunction "1_1") (pintype "passive"))
      (node (ref "C237") (pin "1") (pinfunction "1_1") (pintype "passive"))
      (node (ref "C238") (pin "1") (pinfunction "1_1") (pintype "passive"))
      (node (ref "C239") (pin "1") (pinfunction "1_1") (pintype "passive"))
      (node (ref "C374") (pin "1") (pinfunction "1_1") (pintype "passive"))
      (node (ref "C375") (pin "1") (pinfunction "1_1") (pintype "passive"))
      (node (ref "C377") (pin "1") (pinfunction "1_1") (pintype "passive"))
      (node (ref "C379") (pin "1") (pinfunction "1_1") (pintype "passive"))
      (node (ref "C380") (pin "1") (pinfunction "1_1") (pintype "passive"))
      (node (ref "C381") (pin "1") (pinfunction "1_1") (pintype "passive"))
      (node (ref "C382") (pin "1") (pinfunction "1_1") (pintype "passive"))
      (node (ref "C416") (pin "1") (pinfunction "1_1") (pintype "passive"))
      (node (ref "C417") (pin "1") (pinfunction "1_1") (pintype "passive"))
      (node (ref "C418") (pin "1") (pinfunction "1_1") (pintype "passive"))
      (node (ref "C8") (pin "2") (pinfunction "2_2") (pintype "passive"))
      (node (ref "IC19") (pin "A1") (pinfunction "GND_A1") (pintype "power_in"))
      (node (ref "IC19") (pin "A12") (pinfunction "GND_A12") (pintype "power_in"))
      (node (ref "IC19") (pin "A14") (pinfunction "GND_A14") (pintype "power_in"))
      (node (ref "IC19") (pin "A18") (pinfunction "GND_A18") (pintype "power_in"))
      (node (ref "IC19") (pin "A20") (pinfunction "GND_A20") (pintype "power_in"))
      (node (ref "IC19") (pin "A24") (pinfunction "GND_A24") (pintype "power_in"))
      (node (ref "IC19") (pin "A30") (pinfunction "GND_A30") (pintype "power_in"))
      (node (ref "IC19") (pin "A8") (pinfunction "GND_A8") (pintype "power_in"))
      (node (ref "IC19") (pin "AA13") (pinfunction "GND_AA13") (pintype "power_in"))
      (node (ref "IC19") (pin "AA2") (pinfunction "GND_AA2") (pintype "power_in"))
      (node (ref "IC19") (pin "AA26") (pinfunction "GND_AA26") (pintype "power_in"))
      (node (ref "IC19") (pin "AB15") (pinfunction "GND_AB15") (pintype "power_in"))
      (node (ref "IC19") (pin "AB22") (pinfunction "GND_AB22") (pintype "power_in"))
      (node (ref "IC19") (pin "AB29") (pinfunction "GND_AB29") (pintype "power_in"))
      (node (ref "IC19") (pin "AB5") (pinfunction "GND_AB5") (pintype "power_in"))
      (node (ref "IC19") (pin "AC17") (pinfunction "GND_AC17") (pintype "power_in"))
      (node (ref "IC19") (pin "AC8") (pinfunction "GND_AC8") (pintype "power_in"))
      (node (ref "IC19") (pin "AE2") (pinfunction "GND_AE2") (pintype "power_in"))
      (node (ref "IC19") (pin "AF10") (pinfunction "GND_AF10") (pintype "power_in"))
      (node (ref "IC19") (pin "AF18") (pinfunction "GND_AF18") (pintype "power_in"))
      (node (ref "IC19") (pin "AF20") (pinfunction "GND_AF20") (pintype "power_in"))
      (node (ref "IC19") (pin "AF22") (pinfunction "GND_AF22") (pintype "power_in"))
      (node (ref "IC19") (pin "AF26") (pinfunction "GND_AF26") (pintype "power_in"))
      (node (ref "IC19") (pin "AF29") (pinfunction "GND_AF29") (pintype "power_in"))
      (node (ref "IC19") (pin "AF5") (pinfunction "GND_AF5") (pintype "power_in"))
      (node (ref "IC19") (pin "AG13") (pinfunction "GND_AG13") (pintype "power_in"))
      (node (ref "IC19") (pin "AG15") (pinfunction "GND_AG15") (pintype "power_in"))
      (node (ref "IC19") (pin "AG17") (pinfunction "GND_AG17") (pintype "power_in"))
      (node (ref "IC19") (pin "AG19") (pinfunction "GND_AG19") (pintype "power_in"))
      (node (ref "IC19") (pin "AH11") (pinfunction "GND_AH11") (pintype "power_in"))
      (node (ref "IC19") (pin "AH21") (pinfunction "GND_AH21") (pintype "power_in"))
      (node (ref "IC19") (pin "AH23") (pinfunction "GND_AH23") (pintype "power_in"))
      (node (ref "IC19") (pin "AH28") (pinfunction "GND_AH28") (pintype "power_in"))
      (node (ref "IC19") (pin "AH9") (pinfunction "GND_AH9") (pintype "power_in"))
      (node (ref "IC19") (pin "AJ10") (pinfunction "GND_AJ10") (pintype "power_in"))
      (node (ref "IC19") (pin "AJ12") (pinfunction "GND_AJ12") (pintype "power_in"))
      (node (ref "IC19") (pin "AJ20") (pinfunction "GND_AJ20") (pintype "power_in"))
      (node (ref "IC19") (pin "AJ22") (pinfunction "GND_AJ22") (pintype "power_in"))
      (node (ref "IC19") (pin "AJ24") (pinfunction "GND_AJ24") (pintype "power_in"))
      (node (ref "IC19") (pin "AJ5") (pinfunction "GND_AJ5") (pintype "power_in"))
      (node (ref "IC19") (pin "AJ8") (pinfunction "GND_AJ8") (pintype "power_in"))
      (node (ref "IC19") (pin "AK1") (pinfunction "GND_AK1") (pintype "power_in"))
      (node (ref "IC19") (pin "AK12") (pinfunction "GND_AK12") (pintype "power_in"))
      (node (ref "IC19") (pin "AK14") (pinfunction "GND_AK14") (pintype "power_in"))
      (node (ref "IC19") (pin "AK18") (pinfunction "GND_AK18") (pintype "power_in"))
      (node (ref "IC19") (pin "AK20") (pinfunction "GND_AK20") (pintype "power_in"))
      (node (ref "IC19") (pin "AK24") (pinfunction "GND_AK24") (pintype "power_in"))
      (node (ref "IC19") (pin "AK30") (pinfunction "GND_AK30") (pintype "power_in"))
      (node (ref "IC19") (pin "AK8") (pinfunction "GND_AK8") (pintype "power_in"))
      (node (ref "IC19") (pin "B10") (pinfunction "GND_B10") (pintype "power_in"))
      (node (ref "IC19") (pin "B12") (pinfunction "GND_B12") (pintype "power_in"))
      (node (ref "IC19") (pin "B20") (pinfunction "GND_B20") (pintype "power_in"))
      (node (ref "IC19") (pin "B22") (pinfunction "GND_B22") (pintype "power_in"))
      (node (ref "IC19") (pin "B24") (pinfunction "GND_B24") (pintype "power_in"))
      (node (ref "IC19") (pin "B26") (pinfunction "GND_B26") (pintype "power_in"))
      (node (ref "IC19") (pin "B8") (pinfunction "GND_B8") (pintype "power_in"))
      (node (ref "IC19") (pin "C11") (pinfunction "GND_C11") (pintype "power_in"))
      (node (ref "IC19") (pin "C21") (pinfunction "GND_C21") (pintype "power_in"))
      (node (ref "IC19") (pin "C23") (pinfunction "GND_C23") (pintype "power_in"))
      (node (ref "IC19") (pin "C28") (pinfunction "GND_C28") (pintype "power_in"))
      (node (ref "IC19") (pin "C3") (pinfunction "GND_C3") (pintype "power_in"))
      (node (ref "IC19") (pin "C9") (pinfunction "GND_C9") (pintype "power_in"))
      (node (ref "IC19") (pin "D13") (pinfunction "GND_D13") (pintype "power_in"))
      (node (ref "IC19") (pin "D15") (pinfunction "GND_D15") (pintype "power_in"))
      (node (ref "IC19") (pin "D17") (pinfunction "GND_D17") (pintype "power_in"))
      (node (ref "IC19") (pin "D19") (pinfunction "GND_D19") (pintype "power_in"))
      (node (ref "IC19") (pin "E10") (pinfunction "GND_E10") (pintype "power_in"))
      (node (ref "IC19") (pin "E18") (pinfunction "GND_E18") (pintype "power_in"))
      (node (ref "IC19") (pin "E2") (pinfunction "GND_E2") (pintype "power_in"))
      (node (ref "IC19") (pin "E20") (pinfunction "GND_E20") (pintype "power_in"))
      (node (ref "IC19") (pin "E22") (pinfunction "GND_E22") (pintype "power_in"))
      (node (ref "IC19") (pin "F29") (pinfunction "GND_F29") (pintype "power_in"))
      (node (ref "IC19") (pin "F5") (pinfunction "GND_F5") (pintype "power_in"))
      (node (ref "IC19") (pin "F7") (pinfunction "GND_F7") (pintype "power_in"))
      (node (ref "IC19") (pin "G24") (pinfunction "GND_G24") (pintype "power_in"))
      (node (ref "IC19") (pin "J11") (pinfunction "GND_J11") (pintype "power_in"))
      (node (ref "IC19") (pin "J16") (pinfunction "GND_J16") (pintype "power_in"))
      (node (ref "IC19") (pin "J2") (pinfunction "GND_J2") (pintype "power_in"))
      (node (ref "IC19") (pin "J21") (pinfunction "GND_J21") (pintype "power_in"))
      (node (ref "IC19") (pin "J26") (pinfunction "GND_J26") (pintype "power_in"))
      (node (ref "IC19") (pin "K16") (pinfunction "GND_K16") (pintype "power_in"))
      (node (ref "IC19") (pin "K18") (pinfunction "GND_K18") (pintype "power_in"))
      (node (ref "IC19") (pin "K22") (pinfunction "GND_K22") (pintype "power_in"))
      (node (ref "IC19") (pin "K23") (pinfunction "GND_K23") (pintype "power_in"))
      (node (ref "IC19") (pin "K29") (pinfunction "GND_K29") (pintype "power_in"))
      (node (ref "IC19") (pin "K5") (pinfunction "GND_K5") (pintype "power_in"))
      (node (ref "IC19") (pin "K7") (pinfunction "GND_K7") (pintype "power_in"))
      (node (ref "IC19") (pin "K8") (pinfunction "GND_K8") (pintype "power_in"))
      (node (ref "IC19") (pin "K9") (pinfunction "GND_K9") (pintype "power_in"))
      (node (ref "IC19") (pin "L16") (pinfunction "GND_L16") (pintype "power_in"))
      (node (ref "IC19") (pin "L23") (pinfunction "GND_L23") (pintype "power_in"))
      (node (ref "IC19") (pin "L8") (pinfunction "GND_L8") (pintype "power_in"))
      (node (ref "IC19") (pin "M12") (pinfunction "GND_M12") (pintype "power_in"))
      (node (ref "IC19") (pin "M16") (pinfunction "GND_M16") (pintype "power_in"))
      (node (ref "IC19") (pin "M22") (pinfunction "GND_M22") (pintype "power_in"))
      (node (ref "IC19") (pin "M9") (pinfunction "GND_M9") (pintype "power_in"))
      (node (ref "IC19") (pin "N13") (pinfunction "GND_N13") (pintype "power_in"))
      (node (ref "IC19") (pin "N14") (pinfunction "GND_N14") (pintype "power_in"))
      (node (ref "IC19") (pin "N17") (pinfunction "GND_N17") (pintype "power_in"))
      (node (ref "IC19") (pin "N18") (pinfunction "GND_N18") (pintype "power_in"))
      (node (ref "IC19") (pin "N2") (pinfunction "GND_N2") (pintype "power_in"))
      (node (ref "IC19") (pin "N21") (pinfunction "GND_N21") (pintype "power_in"))
      (node (ref "IC19") (pin "N22") (pinfunction "GND_N22") (pintype "power_in"))
      (node (ref "IC19") (pin "N26") (pinfunction "GND_N26") (pintype "power_in"))
      (node (ref "IC19") (pin "P10") (pinfunction "GND_P10") (pintype "power_in"))
      (node (ref "IC19") (pin "P13") (pinfunction "GND_P13") (pintype "power_in"))
      (node (ref "IC19") (pin "P14") (pinfunction "GND_P14") (pintype "power_in"))
      (node (ref "IC19") (pin "P17") (pinfunction "GND_P17") (pintype "power_in"))
      (node (ref "IC19") (pin "P18") (pinfunction "GND_P18") (pintype "power_in"))
      (node (ref "IC19") (pin "P20") (pinfunction "GND_P20") (pintype "power_in"))
      (node (ref "IC19") (pin "P29") (pinfunction "GND_P29") (pintype "power_in"))
      (node (ref "IC19") (pin "P5") (pinfunction "GND_P5") (pintype "power_in"))
      (node (ref "IC19") (pin "P8") (pinfunction "GND_P8") (pintype "power_in"))
      (node (ref "IC19") (pin "R11") (pinfunction "GND_R11") (pintype "power_in"))
      (node (ref "IC19") (pin "R12") (pinfunction "GND_R12") (pintype "power_in"))
      (node (ref "IC19") (pin "R15") (pinfunction "GND_R15") (pintype "power_in"))
      (node (ref "IC19") (pin "R16") (pinfunction "GND_R16") (pintype "power_in"))
      (node (ref "IC19") (pin "R19") (pinfunction "GND_R19") (pintype "power_in"))
      (node (ref "IC19") (pin "R20") (pinfunction "GND_R20") (pintype "power_in"))
      (node (ref "IC19") (pin "R9") (pinfunction "GND_R9") (pintype "power_in"))
      (node (ref "IC19") (pin "T10") (pinfunction "GND_T10") (pintype "power_in"))
      (node (ref "IC19") (pin "T11") (pinfunction "GND_T11") (pintype "power_in"))
      (node (ref "IC19") (pin "T12") (pinfunction "GND_T12") (pintype "power_in"))
      (node (ref "IC19") (pin "T15") (pinfunction "GND_T15") (pintype "power_in"))
      (node (ref "IC19") (pin "T16") (pinfunction "GND_T16") (pintype "power_in"))
      (node (ref "IC19") (pin "T19") (pinfunction "GND_T19") (pintype "power_in"))
      (node (ref "IC19") (pin "T20") (pinfunction "GND_T20") (pintype "power_in"))
      (node (ref "IC19") (pin "T22") (pinfunction "GND_T22") (pintype "power_in"))
      (node (ref "IC19") (pin "T23") (pinfunction "GND_T23") (pintype "power_in"))
      (node (ref "IC19") (pin "U13") (pinfunction "GND_U13") (pintype "power_in"))
      (node (ref "IC19") (pin "U14") (pinfunction "GND_U14") (pintype "power_in"))
      (node (ref "IC19") (pin "U17") (pinfunction "GND_U17") (pintype "power_in"))
      (node (ref "IC19") (pin "U18") (pinfunction "GND_U18") (pintype "power_in"))
      (node (ref "IC19") (pin "U2") (pinfunction "GND_U2") (pintype "power_in"))
      (node (ref "IC19") (pin "U21") (pinfunction "GND_U21") (pintype "power_in"))
      (node (ref "IC19") (pin "U22") (pinfunction "GND_U22") (pintype "power_in"))
      (node (ref "IC19") (pin "U26") (pinfunction "GND_U26") (pintype "power_in"))
      (node (ref "IC19") (pin "U9") (pinfunction "GND_U9") (pintype "power_in"))
      (node (ref "IC19") (pin "V13") (pinfunction "GND_V13") (pintype "power_in"))
      (node (ref "IC19") (pin "V14") (pinfunction "GND_V14") (pintype "power_in"))
      (node (ref "IC19") (pin "V17") (pinfunction "GND_V17") (pintype "power_in"))
      (node (ref "IC19") (pin "V18") (pinfunction "GND_V18") (pintype "power_in"))
      (node (ref "IC19") (pin "V22") (pinfunction "GND_V22") (pintype "power_in"))
      (node (ref "IC19") (pin "V29") (pinfunction "GND_V29") (pintype "power_in"))
      (node (ref "IC19") (pin "V5") (pinfunction "GND_V5") (pintype "power_in"))
      (node (ref "IC19") (pin "W16") (pinfunction "GND_W16") (pintype "power_in"))
      (node (ref "IC19") (pin "W18") (pinfunction "GND_W18") (pintype "power_in"))
      (node (ref "IC19") (pin "W8") (pinfunction "GND_W8") (pintype "power_in"))
      (node (ref "R13") (pin "1") (pinfunction "1_1") (pintype "passive"))
    )
    (net (code "2") (name "Net-(BATH1-PLUS)") (class "Default")
      (node (ref "BATH1") (pin "1") (pinfunction "PLUS_1") (pintype "input"))
      (node (ref "C8") (pin "1") (pinfunction "1_1") (pintype "passive"))
      (node (ref "IC19") (pin "AB26") (pinfunction "VBATT_AB26") (pintype "input"))
    )
    (net (code "3") (name "Net-(IC19O-RFUSE)") (class "Default")
      (node (ref "IC19") (pin "AB27") (pinfunction "RFUSE_AB27") (pintype "input"))
      (node (ref "R239") (pin "2") (pinfunction "2_2") (pintype "passive"))
    )
    (net (code "4") (name "Net-(IC19O-VFS)") (class "Default")
      (node (ref "C239") (pin "2") (pinfunction "2_2") (pintype "passive"))
      (node (ref "IC19") (pin "AF27") (pinfunction "VFS_AF27") (pintype "input"))
      (node (ref "R97") (pin "2") (pinfunction "2_2") (pintype "passive"))
    )
    (net (code "5") (name "Net-(R13-Pad2)") (class "Default")
      (node (ref "R13") (pin "2") (pinfunction "2_2") (pintype "passive"))
      (node (ref "R239") (pin "1") (pinfunction "1_1") (pintype "passive"))
    )
    (net (code "6") (name "P1V2") (class "Default")
      (node (ref "C134") (pin "2") (pinfunction "2_2") (pintype "passive"))
      (node (ref "C140") (pin "2") (pinfunction "2_2") (pintype "passive"))
      (node (ref "C146") (pin "2") (pinfunction "2_2") (pintype "passive"))
      (node (ref "C147") (pin "2") (pinfunction "2_2") (pintype "passive"))
      (node (ref "C159") (pin "2") (pinfunction "2_2") (pintype "passive"))
      (node (ref "C160") (pin "2") (pinfunction "2_2") (pintype "passive"))
      (node (ref "C174") (pin "2") (pinfunction "2_2") (pintype "passive"))
      (node (ref "C177") (pin "2") (pinfunction "2_2") (pintype "passive"))
      (node (ref "C192") (pin "2") (pinfunction "2_2") (pintype "passive"))
      (node (ref "C193") (pin "2") (pinfunction "2_2") (pintype "passive"))
      (node (ref "C201") (pin "2") (pinfunction "2_2") (pintype "passive"))
      (node (ref "C203") (pin "2") (pinfunction "2_2") (pintype "passive"))
      (node (ref "C223") (pin "2") (pinfunction "2_2") (pintype "passive"))
      (node (ref "C229") (pin "2") (pinfunction "2_2") (pintype "passive"))
      (node (ref "C236") (pin "2") (pinfunction "2_2") (pintype "passive"))
      (node (ref "C237") (pin "2") (pinfunction "2_2") (pintype "passive"))
      (node (ref "C381") (pin "2") (pinfunction "2_2") (pintype "passive"))
      (node (ref "C382") (pin "2") (pinfunction "2_2") (pintype "passive"))
      (node (ref "IC19") (pin "N11") (pinfunction "VCCINT_N11") (pintype "power_in"))
      (node (ref "IC19") (pin "N12") (pinfunction "VCCINT_N12") (pintype "power_in"))
      (node (ref "IC19") (pin "N15") (pinfunction "VCCINT_N15") (pintype "power_in"))
      (node (ref "IC19") (pin "N16") (pinfunction "VCCINT_N16") (pintype "power_in"))
      (node (ref "IC19") (pin "N19") (pinfunction "VCCINT_N19") (pintype "power_in"))
      (node (ref "IC19") (pin "N20") (pinfunction "VCCINT_N20") (pintype "power_in"))
      (node (ref "IC19") (pin "P11") (pinfunction "VCCINT_P11") (pintype "power_in"))
      (node (ref "IC19") (pin "P12") (pinfunction "VCCINT_P12") (pintype "power_in"))
      (node (ref "IC19") (pin "P15") (pinfunction "VCCINT_P15") (pintype "power_in"))
      (node (ref "IC19") (pin "P16") (pinfunction "VCCINT_P16") (pintype "power_in"))
      (node (ref "IC19") (pin "P19") (pinfunction "VCCINT_P19") (pintype "power_in"))
      (node (ref "IC19") (pin "R13") (pinfunction "VCCINT_R13") (pintype "power_in"))
      (node (ref "IC19") (pin "R14") (pinfunction "VCCINT_R14") (pintype "power_in"))
      (node (ref "IC19") (pin "R17") (pinfunction "VCCINT_R17") (pintype "power_in"))
      (node (ref "IC19") (pin "R18") (pinfunction "VCCINT_R18") (pintype "power_in"))
      (node (ref "IC19") (pin "T13") (pinfunction "VCCINT_T13") (pintype "power_in"))
      (node (ref "IC19") (pin "T14") (pinfunction "VCCINT_T14") (pintype "power_in"))
      (node (ref "IC19") (pin "T17") (pinfunction "VCCINT_T17") (pintype "power_in"))
      (node (ref "IC19") (pin "T18") (pinfunction "VCCINT_T18") (pintype "power_in"))
      (node (ref "IC19") (pin "U11") (pinfunction "VCCINT_U11") (pintype "power_in"))
      (node (ref "IC19") (pin "U12") (pinfunction "VCCINT_U12") (pintype "power_in"))
      (node (ref "IC19") (pin "U15") (pinfunction "VCCINT_U15") (pintype "power_in"))
      (node (ref "IC19") (pin "U16") (pinfunction "VCCINT_U16") (pintype "power_in"))
      (node (ref "IC19") (pin "U19") (pinfunction "VCCINT_U19") (pintype "power_in"))
      (node (ref "IC19") (pin "U20") (pinfunction "VCCINT_U20") (pintype "power_in"))
      (node (ref "IC19") (pin "V11") (pinfunction "VCCINT_V11") (pintype "power_in"))
      (node (ref "IC19") (pin "V12") (pinfunction "VCCINT_V12") (pintype "power_in"))
      (node (ref "IC19") (pin "V15") (pinfunction "VCCINT_V15") (pintype "power_in"))
      (node (ref "IC19") (pin "V16") (pinfunction "VCCINT_V16") (pintype "power_in"))
      (node (ref "IC19") (pin "V19") (pinfunction "VCCINT_V19") (pintype "power_in"))
      (node (ref "IC19") (pin "V20") (pinfunction "VCCINT_V20") (pintype "power_in"))
    )
    (net (code "7") (name "P1V5") (class "Default")
      (node (ref "C121") (pin "2") (pinfunction "2_2") (pintype "passive"))
      (node (ref "C141") (pin "2") (pinfunction "2_2") (pintype "passive"))
      (node (ref "C149") (pin "2") (pinfunction "2_2") (pintype "passive"))
      (node (ref "C161") (pin "2") (pinfunction "2_2") (pintype "passive"))
      (node (ref "C178") (pin "2") (pinfunction "2_2") (pintype "passive"))
      (node (ref "C194") (pin "2") (pinfunction "2_2") (pintype "passive"))
      (node (ref "C204") (pin "2") (pinfunction "2_2") (pintype "passive"))
      (node (ref "C230") (pin "2") (pinfunction "2_2") (pintype "passive"))
      (node (ref "C238") (pin "2") (pinfunction "2_2") (pintype "passive"))
      (node (ref "C416") (pin "2") (pinfunction "2_2") (pintype "passive"))
      (node (ref "IC19") (pin "B28") (pinfunction "VCCO_5_B28") (pintype "power_in"))
      (node (ref "IC19") (pin "B4") (pinfunction "VCCO_4_B4") (pintype "power_in"))
      (node (ref "IC19") (pin "C2") (pinfunction "VCCO_4_C2") (pintype "power_in"))
      (node (ref "IC19") (pin "D29") (pinfunction "VCCO_5_D29") (pintype "power_in"))
      (node (ref "IC19") (pin "G2") (pinfunction "VCCO_4_G2") (pintype "power_in"))
      (node (ref "IC19") (pin "G26") (pinfunction "VCCO_5_G26") (pintype "power_in"))
      (node (ref "IC19") (pin "H29") (pinfunction "VCCO_5_H29") (pintype "power_in"))
      (node (ref "IC19") (pin "H5") (pinfunction "VCCO_4_H5") (pintype "power_in"))
      (node (ref "IC19") (pin "J25") (pinfunction "VCCO_5_J25") (pintype "power_in"))
      (node (ref "IC19") (pin "K24") (pinfunction "VCCO_5_K24") (pintype "power_in"))
      (node (ref "IC19") (pin "K6") (pinfunction "VCCO_4_K6") (pintype "power_in"))
      (node (ref "IC19") (pin "L2") (pinfunction "VCCO_4_L2") (pintype "power_in"))
      (node (ref "IC19") (pin "L26") (pinfunction "VCCO_5_L26") (pintype "power_in"))
      (node (ref "IC19") (pin "M29") (pinfunction "VCCO_5_M29") (pintype "power_in"))
      (node (ref "IC19") (pin "M5") (pinfunction "VCCO_4_M5") (pintype "power_in"))
    )
    (net (code "8") (name "P2V5") (class "Default")
      (node (ref "C120") (pin "2") (pinfunction "2_2") (pintype "passive"))
      (node (ref "C122") (pin "2") (pinfunction "2_2") (pintype "passive"))
      (node (ref "C123") (pin "2") (pinfunction "2_2") (pintype "passive"))
      (node (ref "C124") (pin "2") (pinfunction "2_2") (pintype "passive"))
      (node (ref "C126") (pin "2") (pinfunction "2_2") (pintype "passive"))
      (node (ref "C129") (pin "2") (pinfunction "2_2") (pintype "passive"))
      (node (ref "C142") (pin "2") (pinfunction "2_2") (pintype "passive"))
      (node (ref "C150") (pin "2") (pinfunction "2_2") (pintype "passive"))
      (node (ref "C151") (pin "2") (pinfunction "2_2") (pintype "passive"))
      (node (ref "C168") (pin "2") (pinfunction "2_2") (pintype "passive"))
      (node (ref "C187") (pin "2") (pinfunction "2_2") (pintype "passive"))
      (node (ref "C188") (pin "2") (pinfunction "2_2") (pintype "passive"))
      (node (ref "C196") (pin "2") (pinfunction "2_2") (pintype "passive"))
      (node (ref "C205") (pin "2") (pinfunction "2_2") (pintype "passive"))
      (node (ref "C215") (pin "2") (pinfunction "2_2") (pintype "passive"))
      (node (ref "C231") (pin "2") (pinfunction "2_2") (pintype "passive"))
      (node (ref "C374") (pin "2") (pinfunction "2_2") (pintype "passive"))
      (node (ref "C375") (pin "2") (pinfunction "2_2") (pintype "passive"))
      (node (ref "C418") (pin "2") (pinfunction "2_2") (pintype "passive"))
      (node (ref "IC19") (pin "AA12") (pinfunction "VCCO_2_AA12") (pintype "power_in"))
      (node (ref "IC19") (pin "AA16") (pinfunction "VCCO_2_AA16") (pintype "power_in"))
      (node (ref "IC19") (pin "AA20") (pinfunction "VCCO_2_AA20") (pintype "power_in"))
      (node (ref "IC19") (pin "AC10") (pinfunction "VCCO_2_AC10") (pintype "power_in"))
      (node (ref "IC19") (pin "AC18") (pinfunction "VCCO_2_AC18") (pintype "power_in"))
      (node (ref "IC19") (pin "AD13") (pinfunction "VCCO_2_AD13") (pintype "power_in"))
      (node (ref "IC19") (pin "AD21") (pinfunction "VCCO_2_AD21") (pintype "power_in"))
      (node (ref "IC19") (pin "AD23") (pinfunction "VCCO_2_AD23") (pintype "power_in"))
      (node (ref "IC19") (pin "AE16") (pinfunction "VCCO_2_AE16") (pintype "power_in"))
      (node (ref "IC19") (pin "AF8") (pinfunction "VCCO_2_AF8") (pintype "power_in"))
      (node (ref "IC19") (pin "AH25") (pinfunction "VCCO_2_AH25") (pintype "power_in"))
      (node (ref "IC19") (pin "AJ16") (pinfunction "VCCO_2_AJ16") (pintype "power_in"))
      (node (ref "IC19") (pin "AJ7") (pinfunction "VCCO_2_AJ7") (pintype "power_in"))
      (node (ref "IC19") (pin "B16") (pinfunction "VCCO_0_B16") (pintype "power_in"))
      (node (ref "IC19") (pin "C25") (pinfunction "VCCO_0_C25") (pintype "power_in"))
      (node (ref "IC19") (pin "C7") (pinfunction "VCCO_0_C7") (pintype "power_in"))
      (node (ref "IC19") (pin "F16") (pinfunction "VCCO_0_F16") (pintype "power_in"))
      (node (ref "IC19") (pin "G13") (pinfunction "VCCO_0_G13") (pintype "power_in"))
      (node (ref "IC19") (pin "G23") (pinfunction "VCCO_0_G23") (pintype "power_in"))
      (node (ref "IC19") (pin "G8") (pinfunction "VCCO_0_G8") (pintype "power_in"))
      (node (ref "IC19") (pin "H10") (pinfunction "VCCO_0_H10") (pintype "power_in"))
      (node (ref "IC19") (pin "H20") (pinfunction "VCCO_0_H20") (pintype "power_in"))
      (node (ref "IC19") (pin "J17") (pinfunction "VCCO_0_J17") (pintype "power_in"))
      (node (ref "IC19") (pin "K13") (pinfunction "VCCO_0_K13") (pintype "power_in"))
      (node (ref "IC19") (pin "L15") (pinfunction "VCCO_0_L15") (pintype "power_in"))
      (node (ref "IC19") (pin "L9") (pinfunction "VCCO_0_L9") (pintype "power_in"))
      (node (ref "IC19") (pin "M17") (pinfunction "VCCO_0_M17") (pintype "power_in"))
      (node (ref "IC19") (pin "M21") (pinfunction "VCCO_0_M21") (pintype "power_in"))
    )
    (net (code "9") (name "P3V3") (class "Default")
      (node (ref "C130") (pin "2") (pinfunction "2_2") (pintype "passive"))
      (node (ref "C131") (pin "2") (pinfunction "2_2") (pintype "passive"))
      (node (ref "C133") (pin "2") (pinfunction "2_2") (pintype "passive"))
      (node (ref "C143") (pin "2") (pinfunction "2_2") (pintype "passive"))
      (node (ref "C144") (pin "2") (pinfunction "2_2") (pintype "passive"))
      (node (ref "C145") (pin "2") (pinfunction "2_2") (pintype "passive"))
      (node (ref "C155") (pin "2") (pinfunction "2_2") (pintype "passive"))
      (node (ref "C156") (pin "2") (pinfunction "2_2") (pintype "passive"))
      (node (ref "C158") (pin "2") (pinfunction "2_2") (pintype "passive"))
      (node (ref "C170") (pin "2") (pinfunction "2_2") (pintype "passive"))
      (node (ref "C171") (pin "2") (pinfunction "2_2") (pintype "passive"))
      (node (ref "C172") (pin "2") (pinfunction "2_2") (pintype "passive"))
      (node (ref "C189") (pin "2") (pinfunction "2_2") (pintype "passive"))
      (node (ref "C190") (pin "2") (pinfunction "2_2") (pintype "passive"))
      (node (ref "C191") (pin "2") (pinfunction "2_2") (pintype "passive"))
      (node (ref "C197") (pin "2") (pinfunction "2_2") (pintype "passive"))
      (node (ref "C198") (pin "2") (pinfunction "2_2") (pintype "passive"))
      (node (ref "C199") (pin "2") (pinfunction "2_2") (pintype "passive"))
      (node (ref "C217") (pin "2") (pinfunction "2_2") (pintype "passive"))
      (node (ref "C221") (pin "2") (pinfunction "2_2") (pintype "passive"))
      (node (ref "C222") (pin "2") (pinfunction "2_2") (pintype "passive"))
      (node (ref "C232") (pin "2") (pinfunction "2_2") (pintype "passive"))
      (node (ref "C233") (pin "2") (pinfunction "2_2") (pintype "passive"))
      (node (ref "C234") (pin "2") (pinfunction "2_2") (pintype "passive"))
      (node (ref "C377") (pin "2") (pinfunction "2_2") (pintype "passive"))
      (node (ref "C379") (pin "2") (pinfunction "2_2") (pintype "passive"))
      (node (ref "C380") (pin "2") (pinfunction "2_2") (pintype "passive"))
      (node (ref "C417") (pin "2") (pinfunction "2_2") (pintype "passive"))
      (node (ref "IC19") (pin "AA23") (pinfunction "VCCO_1_AA23") (pintype "power_in"))
      (node (ref "IC19") (pin "AA8") (pinfunction "VCCO_3_AA8") (pintype "power_in"))
      (node (ref "IC19") (pin "AB24") (pinfunction "VCCAUX_AB24") (pintype "power_in"))
      (node (ref "IC19") (pin "AC2") (pinfunction "VCCO_3_AC2") (pintype "power_in"))
      (node (ref "IC19") (pin "AC26") (pinfunction "VCCO_1_AC26") (pintype "power_in"))
      (node (ref "IC19") (pin "AC7") (pinfunction "VCCAUX_AC7") (pintype "power_in"))
      (node (ref "IC19") (pin "AD29") (pinfunction "VCCO_1_AD29") (pintype "power_in"))
      (node (ref "IC19") (pin "AD5") (pinfunction "VCCO_3_AD5") (pintype "power_in"))
      (node (ref "IC19") (pin "AG2") (pinfunction "VCCO_3_AG2") (pintype "power_in"))
      (node (ref "IC19") (pin "AG23") (pinfunction "VCCAUX_AG23") (pintype "power_in"))
      (node (ref "IC19") (pin "AG9") (pinfunction "VCCAUX_AG9") (pintype "power_in"))
      (node (ref "IC19") (pin "AH29") (pinfunction "VCCO_1_AH29") (pintype "power_in"))
      (node (ref "IC19") (pin "AJ27") (pinfunction "VCCO_1_AJ27") (pintype "power_in"))
      (node (ref "IC19") (pin "AJ3") (pinfunction "VCCO_3_AJ3") (pintype "power_in"))
      (node (ref "IC19") (pin "D23") (pinfunction "VCCAUX_D23") (pintype "power_in"))
      (node (ref "IC19") (pin "D9") (pinfunction "VCCAUX_D9") (pintype "power_in"))
      (node (ref "IC19") (pin "G6") (pinfunction "VCCAUX_G6") (pintype "power_in"))
      (node (ref "IC19") (pin "H24") (pinfunction "VCCAUX_H24") (pintype "power_in"))
      (node (ref "IC19") (pin "J15") (pinfunction "VCCAUX_J15") (pintype "power_in"))
      (node (ref "IC19") (pin "J23") (pinfunction "VCCAUX_J23") (pintype "power_in"))
      (node (ref "IC19") (pin "J7") (pinfunction "VCCAUX_J7") (pintype "power_in"))
      (node (ref "IC19") (pin "J9") (pinfunction "VCCAUX_J9") (pintype "power_in"))
      (node (ref "IC19") (pin "L22") (pinfunction "VCCAUX_L22") (pintype "power_in"))
      (node (ref "IC19") (pin "M11") (pinfunction "VCCAUX_M11") (pintype "power_in"))
      (node (ref "IC19") (pin "M14") (pinfunction "VCCAUX_M14") (pintype "power_in"))
      (node (ref "IC19") (pin "M25") (pinfunction "VCCAUX_M25") (pintype "power_in"))
      (node (ref "IC19") (pin "M8") (pinfunction "VCCO_3_M8") (pintype "power_in"))
      (node (ref "IC19") (pin "N23") (pinfunction "VCCO_1_N23") (pintype "power_in"))
      (node (ref "IC19") (pin "N6") (pinfunction "VCCAUX_N6") (pintype "power_in"))
      (node (ref "IC19") (pin "P21") (pinfunction "VCCO_1_P21") (pintype "power_in"))
      (node (ref "IC19") (pin "P9") (pinfunction "VCCO_3_P9") (pintype "power_in"))
      (node (ref "IC19") (pin "R10") (pinfunction "VCCAUX_R10") (pintype "power_in"))
      (node (ref "IC19") (pin "R2") (pinfunction "VCCO_3_R2") (pintype "power_in"))
      (node (ref "IC19") (pin "R23") (pinfunction "VCCO_1_R23") (pintype "power_in"))
      (node (ref "IC19") (pin "R26") (pinfunction "VCCO_1_R26") (pintype "power_in"))
      (node (ref "IC19") (pin "R8") (pinfunction "VCCO_3_R8") (pintype "power_in"))
      (node (ref "IC19") (pin "T21") (pinfunction "VCCAUX_T21") (pintype "power_in"))
      (node (ref "IC19") (pin "T29") (pinfunction "VCCO_1_T29") (pintype "power_in"))
      (node (ref "IC19") (pin "T5") (pinfunction "VCCO_3_T5") (pintype "power_in"))
      (node (ref "IC19") (pin "U10") (pinfunction "VCCAUX_U10") (pintype "power_in"))
      (node (ref "IC19") (pin "U23") (pinfunction "VCCO_1_U23") (pintype "power_in"))
      (node (ref "IC19") (pin "U8") (pinfunction "VCCO_3_U8") (pintype "power_in"))
      (node (ref "IC19") (pin "V21") (pinfunction "VCCAUX_V21") (pintype "power_in"))
      (node (ref "IC19") (pin "V25") (pinfunction "VCCAUX_V25") (pintype "power_in"))
      (node (ref "IC19") (pin "V6") (pinfunction "VCCAUX_V6") (pintype "power_in"))
      (node (ref "IC19") (pin "W13") (pinfunction "VCCAUX_W13") (pintype "power_in"))
      (node (ref "IC19") (pin "W15") (pinfunction "VCCAUX_W15") (pintype "power_in"))
      (node (ref "IC19") (pin "W17") (pinfunction "VCCAUX_W17") (pintype "power_in"))
      (node (ref "IC19") (pin "W2") (pinfunction "VCCO_3_W2") (pintype "power_in"))
      (node (ref "IC19") (pin "W23") (pinfunction "VCCO_1_W23") (pintype "power_in"))
      (node (ref "IC19") (pin "W26") (pinfunction "VCCO_1_W26") (pintype "power_in"))
      (node (ref "IC19") (pin "Y10") (pinfunction "VCCO_3_Y10") (pintype "power_in"))
      (node (ref "IC19") (pin "Y18") (pinfunction "VCCAUX_Y18") (pintype "power_in"))
      (node (ref "IC19") (pin "Y29") (pinfunction "VCCO_1_Y29") (pintype "power_in"))
      (node (ref "IC19") (pin "Y5") (pinfunction "VCCO_3_Y5") (pintype "power_in"))
      (node (ref "R97") (pin "1") (pinfunction "1_1") (pintype "passive"))
    )
  )
)
